# DSO_Control.net
KiCad netlist of a schematic drawn in Altium Designer
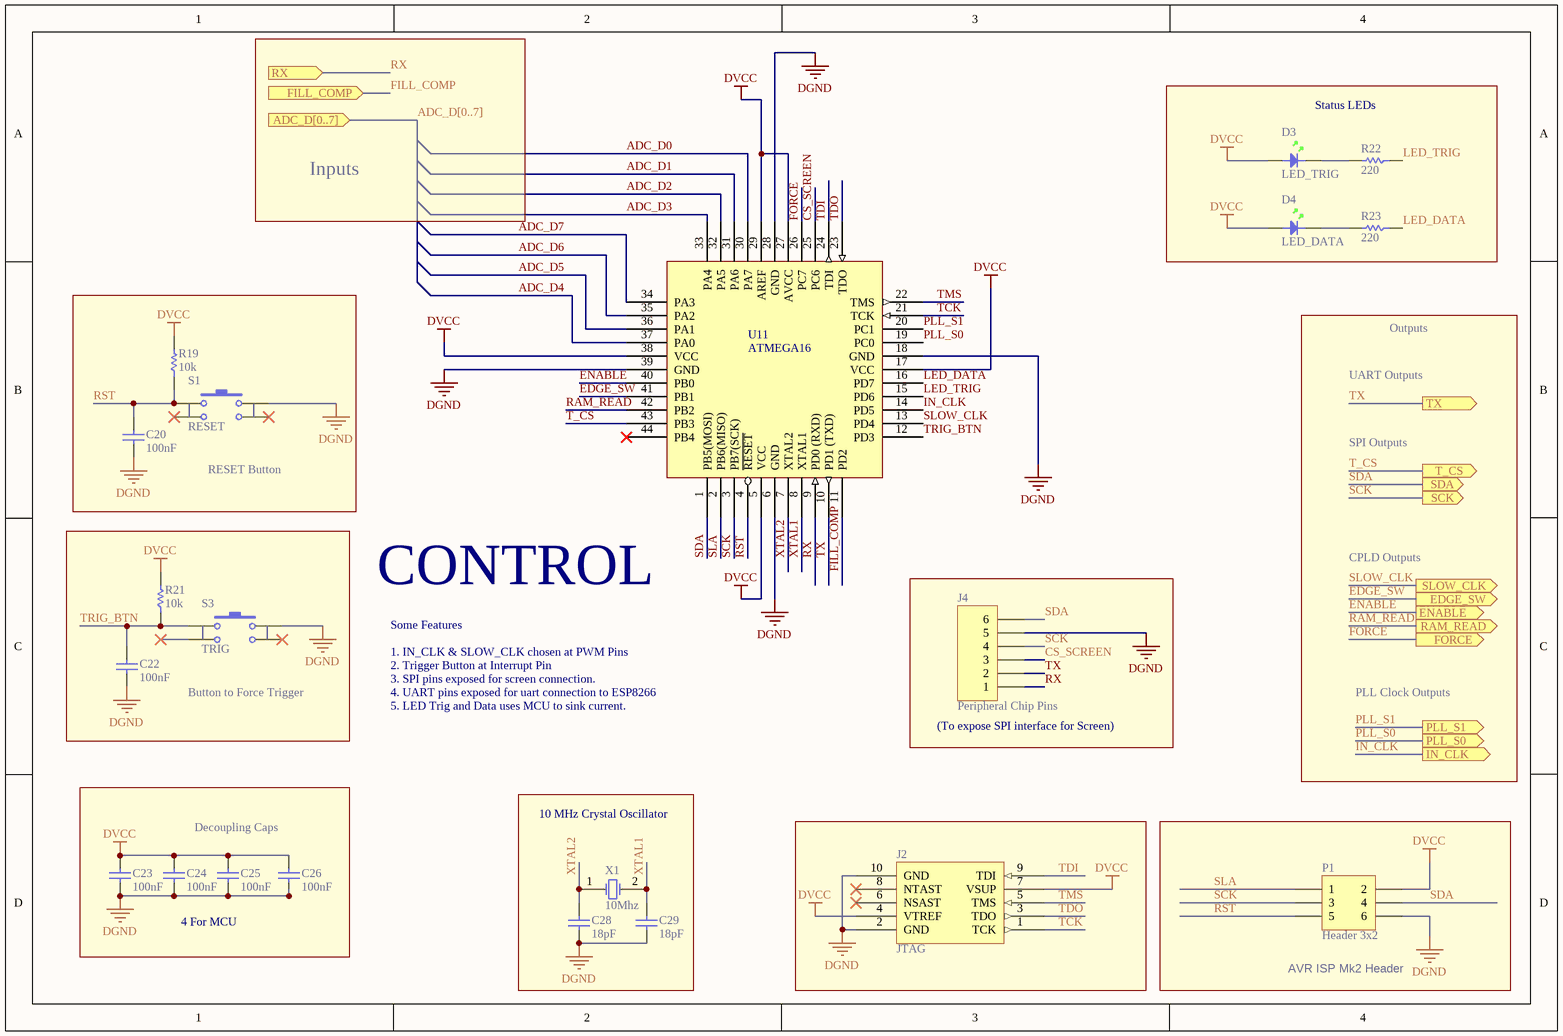
[diagram p0: DSO_Control.SchDoc]

(export (version "E")
  (design (tool "Eeschema 10.0.6"))
  (components
    (comp (ref "C20")
      (value "100nF")
      (footprint "0805C")
      (description "Capacitor")
      (fields (field (name "REVIEWED BY") "RM - 2018/08/05"))
      (libsource (lib "DSO") (part "C"))
    )
    (comp (ref "C22")
      (value "100nF")
      (footprint "0805C")
      (description "Capacitor")
      (fields (field (name "REVIEWED BY") "RM - 2018/08/05"))
      (libsource (lib "DSO") (part "C"))
    )
    (comp (ref "C23")
      (value "100nF")
      (footprint "0805C")
      (description "Capacitor")
      (fields (field (name "REVIEWED BY") "RM - 2018/08/05"))
      (libsource (lib "DSO") (part "C"))
    )
    (comp (ref "C24")
      (value "100nF")
      (footprint "0805C")
      (description "Capacitor")
      (fields (field (name "REVIEWED BY") "RM - 2018/08/05"))
      (libsource (lib "DSO") (part "C"))
    )
    (comp (ref "C25")
      (value "100nF")
      (footprint "0805C")
      (description "Capacitor")
      (fields (field (name "REVIEWED BY") "RM - 2018/08/05"))
      (libsource (lib "DSO") (part "C"))
    )
    (comp (ref "C26")
      (value "100nF")
      (footprint "0805C")
      (description "Capacitor")
      (fields (field (name "REVIEWED BY") "RM - 2018/08/05"))
      (libsource (lib "DSO") (part "C"))
    )
    (comp (ref "C28")
      (value "18pF")
      (footprint "0805C")
      (description "Capacitor")
      (fields (field (name "REVIEWED BY") "RM - 2018/08/05"))
      (libsource (lib "DSO") (part "C"))
    )
    (comp (ref "C29")
      (value "18pF")
      (footprint "0805C")
      (description "Capacitor")
      (fields (field (name "REVIEWED BY") "RM - 2018/08/05"))
      (libsource (lib "DSO") (part "C"))
    )
    (comp (ref "D3")
      (value "LED_TRIG")
      (footprint "0805D-GREEN")
      (description "Light Emitting Diode")
      (fields (field (name "REVIEWED BY") "RM - 2018/08/05"))
      (libsource (lib "DSO") (part "LED GREEN"))
    )
    (comp (ref "D4")
      (value "LED_DATA")
      (footprint "0805D-GREEN")
      (description "Light Emitting Diode")
      (fields (field (name "REVIEWED BY") "RM - 2018/08/05"))
      (libsource (lib "DSO") (part "LED GREEN"))
    )
    (comp (ref "J2")
      (value "JTAG")
      (footprint "BOXEDVERT10")
      (description "JTAG_CON")
      (fields (field (name "REVIEWED BY") "RM - 2018/08/05"))
      (libsource (lib "DSO") (part "JTAG_CON"))
    )
    (comp (ref "J4")
      (value "Peripheral Chip Pins")
      (footprint "HDR1X6")
      (description "Header, 6-Pin")
      (libsource (lib "DSO") (part "Header 6"))
    )
    (comp (ref "P1")
      (value "Header 3x2")
      (footprint "HDR3x2")
      (description "Header, 5-Pin")
      (fields (field (name "REVIEWED BY") "RM - 2018/08/05"))
      (libsource (lib "DSO") (part "Header 3x2"))
    )
    (comp (ref "R19")
      (value "10k")
      (footprint "0805")
      (description "Resistor")
      (fields (field (name "REVIEWED BY") "RM - 2018/08/05"))
      (libsource (lib "DSO") (part "R"))
    )
    (comp (ref "R21")
      (value "10k")
      (footprint "0805")
      (description "Resistor")
      (fields (field (name "REVIEWED BY") "RM - 2018/08/05"))
      (libsource (lib "DSO") (part "R"))
    )
    (comp (ref "R22")
      (value "220")
      (footprint "0805")
      (description "Resistor")
      (fields (field (name "REVIEWED BY") "RM - 2018/08/05"))
      (libsource (lib "DSO") (part "R"))
    )
    (comp (ref "R23")
      (value "220")
      (footprint "0805")
      (description "Resistor")
      (fields (field (name "REVIEWED BY") "RM - 2018/08/05"))
      (libsource (lib "DSO") (part "R"))
    )
    (comp (ref "S1")
      (value "RESET")
      (footprint "SPST PB SWITCH SMD")
      (description "Momentary Push Button Switch 1P 1T 2pins")
      (fields (field (name "REVIEWED BY") "RM - 2018/08/05"))
      (libsource (lib "DSO") (part "SW_PB_1P1T4"))
    )
    (comp (ref "S3")
      (value "TRIG")
      (footprint "SPST PB SWITCH SMD")
      (description "Momentary Push Button Switch 1P 1T 2pins")
      (fields (field (name "REVIEWED BY") "RM - 2018/08/05"))
      (libsource (lib "DSO") (part "SW_PB_1P1T4"))
    )
    (comp (ref "U11")
      (value "ATMEGA16")
      (footprint "QFP-48")
      (description "ATMEGA16 Microcontroller")
      (fields (field (name "REVIEWED BY") "RM - 2018/08/05"))
      (libsource (lib "DSO") (part "ATMEGA16"))
    )
    (comp (ref "X1")
      (value "10Mhz")
      (footprint "XTAL_FLAT_SMD")
      (description "Crystal Oscillator")
      (fields (field (name "REVIEWED BY") "RM - 2018/08/05"))
      (libsource (lib "DSO") (part "XTAL"))
    )
  )
  (nets
    (net (code "1") (name "/ADC_D0") (class "Default")
      (node (ref "U11") (pin "30") (pinfunction "PA7_30") (pintype "passive"))
    )
    (net (code "2") (name "/ADC_D1") (class "Default")
      (node (ref "U11") (pin "31") (pinfunction "PA6_31") (pintype "passive"))
    )
    (net (code "3") (name "/ADC_D2") (class "Default")
      (node (ref "U11") (pin "32") (pinfunction "PA5_32") (pintype "passive"))
    )
    (net (code "4") (name "/ADC_D3") (class "Default")
      (node (ref "U11") (pin "33") (pinfunction "PA4_33") (pintype "passive"))
    )
    (net (code "5") (name "/ADC_D4") (class "Default")
      (node (ref "U11") (pin "37") (pinfunction "PA0_37") (pintype "passive"))
    )
    (net (code "6") (name "/ADC_D5") (class "Default")
      (node (ref "U11") (pin "36") (pinfunction "PA1_36") (pintype "passive"))
    )
    (net (code "7") (name "/ADC_D6") (class "Default")
      (node (ref "U11") (pin "35") (pinfunction "PA2_35") (pintype "passive"))
    )
    (net (code "8") (name "/ADC_D7") (class "Default")
      (node (ref "U11") (pin "34") (pinfunction "PA3_34") (pintype "passive"))
    )
    (net (code "10") (name "/CS_SCREEN") (class "Default")
      (node (ref "J4") (pin "3") (pinfunction "3_3") (pintype "passive"))
      (node (ref "U11") (pin "25") (pinfunction "PC6_25") (pintype "passive"))
    )
    (net (code "11") (name "/EDGE_SW") (class "Default")
      (node (ref "U11") (pin "41") (pinfunction "PB1_41") (pintype "passive"))
    )
    (net (code "12") (name "/ENABLE") (class "Default")
      (node (ref "U11") (pin "40") (pinfunction "PB0_40") (pintype "passive"))
    )
    (net (code "13") (name "/FILL_COMP") (class "Default")
      (node (ref "U11") (pin "11") (pinfunction "PD2_11") (pintype "passive"))
    )
    (net (code "14") (name "/FORCE") (class "Default")
      (node (ref "U11") (pin "26") (pinfunction "PC7_26") (pintype "passive"))
    )
    (net (code "15") (name "/IN_CLK") (class "Default")
      (node (ref "U11") (pin "14") (pinfunction "PD5_14") (pintype "passive"))
    )
    (net (code "16") (name "/LED_DATA") (class "Default")
      (node (ref "R23") (pin "1") (pintype "passive"))
      (node (ref "U11") (pin "16") (pinfunction "PD7_16") (pintype "passive"))
    )
    (net (code "17") (name "/LED_TRIG") (class "Default")
      (node (ref "R22") (pin "1") (pintype "passive"))
      (node (ref "U11") (pin "15") (pinfunction "PD6_15") (pintype "passive"))
    )
    (net (code "18") (name "/PLL_S0") (class "Default")
      (node (ref "U11") (pin "19") (pinfunction "PC0_19") (pintype "passive"))
    )
    (net (code "19") (name "/PLL_S1") (class "Default")
      (node (ref "U11") (pin "20") (pinfunction "PC1_20") (pintype "passive"))
    )
    (net (code "20") (name "/RAM_READ") (class "Default")
      (node (ref "U11") (pin "42") (pinfunction "PB2_42") (pintype "passive"))
    )
    (net (code "21") (name "/RST") (class "Default")
      (node (ref "C20") (pin "1") (pinfunction "1_1") (pintype "passive"))
      (node (ref "P1") (pin "5") (pinfunction "5_5") (pintype "passive"))
      (node (ref "R19") (pin "1") (pintype "passive"))
      (node (ref "S1") (pin "1") (pinfunction "1_1") (pintype "passive"))
      (node (ref "U11") (pin "4") (pinfunction "~{RESET}_4") (pintype "passive"))
    )
    (net (code "22") (name "/RX") (class "Default")
      (node (ref "J4") (pin "1") (pinfunction "1_1") (pintype "passive"))
      (node (ref "U11") (pin "9") (pinfunction "PD0_(RXD)_9") (pintype "input"))
    )
    (net (code "23") (name "/SCK") (class "Default")
      (node (ref "J4") (pin "4") (pinfunction "4_4") (pintype "passive"))
      (node (ref "P1") (pin "3") (pinfunction "3_3") (pintype "passive"))
      (node (ref "U11") (pin "3") (pinfunction "PB7(SCK)_3") (pintype "passive"))
    )
    (net (code "24") (name "/SDA") (class "Default")
      (node (ref "J4") (pin "6") (pinfunction "6_6") (pintype "passive"))
      (node (ref "P1") (pin "4") (pinfunction "4_4") (pintype "passive"))
      (node (ref "U11") (pin "1") (pinfunction "PB5(MOSI)_1") (pintype "passive"))
    )
    (net (code "25") (name "/SLA") (class "Default")
      (node (ref "P1") (pin "1") (pinfunction "1_1") (pintype "passive"))
      (node (ref "U11") (pin "2") (pinfunction "PB6(MISO)_2") (pintype "passive"))
    )
    (net (code "26") (name "/SLOW_CLK") (class "Default")
      (node (ref "U11") (pin "13") (pinfunction "PD4_13") (pintype "passive"))
    )
    (net (code "27") (name "/TCK") (class "Default")
      (node (ref "J2") (pin "1") (pinfunction "TCK_1") (pintype "output"))
      (node (ref "U11") (pin "21") (pinfunction "TCK_21") (pintype "input"))
    )
    (net (code "28") (name "/TDI") (class "Default")
      (node (ref "J2") (pin "9") (pinfunction "TDI_9") (pintype "input"))
      (node (ref "U11") (pin "24") (pinfunction "TDI_24") (pintype "output"))
    )
    (net (code "29") (name "/TDO") (class "Default")
      (node (ref "J2") (pin "3") (pinfunction "TDO_3") (pintype "output"))
      (node (ref "U11") (pin "23") (pinfunction "TDO_23") (pintype "input"))
    )
    (net (code "30") (name "/TMS") (class "Default")
      (node (ref "J2") (pin "5") (pinfunction "TMS_5") (pintype "input"))
      (node (ref "U11") (pin "22") (pinfunction "TMS_22") (pintype "output"))
    )
    (net (code "31") (name "/TRIG_BTN") (class "Default")
      (node (ref "C22") (pin "1") (pinfunction "1_1") (pintype "passive"))
      (node (ref "R21") (pin "1") (pintype "passive"))
      (node (ref "S3") (pin "1") (pinfunction "1_1") (pintype "passive"))
      (node (ref "U11") (pin "12") (pinfunction "PD3_12") (pintype "passive"))
    )
    (net (code "32") (name "/TX") (class "Default")
      (node (ref "J4") (pin "2") (pinfunction "2_2") (pintype "passive"))
      (node (ref "U11") (pin "10") (pinfunction "PD1_(TXD)_10") (pintype "output"))
    )
    (net (code "33") (name "/T_CS") (class "Default")
      (node (ref "U11") (pin "43") (pinfunction "PB3_43") (pintype "passive"))
    )
    (net (code "34") (name "/XTAL1") (class "Default")
      (node (ref "C29") (pin "1") (pinfunction "1_1") (pintype "passive"))
      (node (ref "U11") (pin "8") (pinfunction "XTAL1_8") (pintype "passive"))
      (node (ref "X1") (pin "2") (pinfunction "OSC2_2") (pintype "passive"))
    )
    (net (code "35") (name "/XTAL2") (class "Default")
      (node (ref "C28") (pin "1") (pinfunction "1_1") (pintype "passive"))
      (node (ref "U11") (pin "7") (pinfunction "XTAL2_7") (pintype "passive"))
      (node (ref "X1") (pin "1") (pinfunction "OSC1_1") (pintype "passive"))
    )
    (net (code "36") (name "DGND") (class "Default")
      (node (ref "C20") (pin "2") (pinfunction "2_2") (pintype "passive"))
      (node (ref "C22") (pin "2") (pinfunction "2_2") (pintype "passive"))
      (node (ref "C23") (pin "2") (pinfunction "2_2") (pintype "passive"))
      (node (ref "C24") (pin "2") (pinfunction "2_2") (pintype "passive"))
      (node (ref "C25") (pin "2") (pinfunction "2_2") (pintype "passive"))
      (node (ref "C26") (pin "2") (pinfunction "2_2") (pintype "passive"))
      (node (ref "C28") (pin "2") (pinfunction "2_2") (pintype "passive"))
      (node (ref "C29") (pin "2") (pinfunction "2_2") (pintype "passive"))
      (node (ref "J2") (pin "10") (pinfunction "GND_10") (pintype "passive"))
      (node (ref "J2") (pin "2") (pinfunction "GND_2") (pintype "passive"))
      (node (ref "J4") (pin "5") (pinfunction "5_5") (pintype "passive"))
      (node (ref "P1") (pin "6") (pinfunction "6_6") (pintype "passive"))
      (node (ref "S1") (pin "2") (pinfunction "2_2") (pintype "passive"))
      (node (ref "S3") (pin "2") (pinfunction "2_2") (pintype "passive"))
      (node (ref "U11") (pin "18") (pinfunction "GND_18") (pintype "passive"))
      (node (ref "U11") (pin "28") (pinfunction "GND_28") (pintype "passive"))
      (node (ref "U11") (pin "39") (pinfunction "GND_39") (pintype "passive"))
      (node (ref "U11") (pin "6") (pinfunction "GND_6") (pintype "passive"))
    )
    (net (code "37") (name "DVCC") (class "Default")
      (node (ref "C23") (pin "1") (pinfunction "1_1") (pintype "passive"))
      (node (ref "C24") (pin "1") (pinfunction "1_1") (pintype "passive"))
      (node (ref "C25") (pin "1") (pinfunction "1_1") (pintype "passive"))
      (node (ref "C26") (pin "1") (pinfunction "1_1") (pintype "passive"))
      (node (ref "D3") (pin "A") (pinfunction "A_A") (pintype "passive"))
      (node (ref "D4") (pin "A") (pinfunction "A_A") (pintype "passive"))
      (node (ref "J2") (pin "4") (pinfunction "VTREF_4") (pintype "power_in"))
      (node (ref "J2") (pin "7") (pinfunction "VSUP_7") (pintype "passive"))
      (node (ref "P1") (pin "2") (pinfunction "2_2") (pintype "passive"))
      (node (ref "R19") (pin "2") (pintype "passive"))
      (node (ref "R21") (pin "2") (pintype "passive"))
      (node (ref "U11") (pin "17") (pinfunction "VCC_17") (pintype "passive"))
      (node (ref "U11") (pin "27") (pinfunction "AVCC_27") (pintype "passive"))
      (node (ref "U11") (pin "29") (pinfunction "AREF_29") (pintype "passive"))
      (node (ref "U11") (pin "38") (pinfunction "VCC_38") (pintype "passive"))
      (node (ref "U11") (pin "5") (pinfunction "VCC_5") (pintype "passive"))
    )
    (net (code "38") (name "Net-(D3-PadK)") (class "Default")
      (node (ref "D3") (pin "K") (pinfunction "K_K") (pintype "passive"))
      (node (ref "R22") (pin "2") (pintype "passive"))
    )
    (net (code "39") (name "Net-(D4-PadK)") (class "Default")
      (node (ref "D4") (pin "K") (pinfunction "K_K") (pintype "passive"))
      (node (ref "R23") (pin "2") (pintype "passive"))
    )
    (net (code "40") (name "unconnected-(J2-NSAST-Pad6)") (class "Default")
      (node (ref "J2") (pin "6") (pinfunction "NSAST_6") (pintype "passive+no_connect"))
    )
    (net (code "41") (name "unconnected-(J2-NTAST-Pad8)") (class "Default")
      (node (ref "J2") (pin "8") (pinfunction "NTAST_8") (pintype "passive+no_connect"))
    )
    (net (code "42") (name "unconnected-(S1-Pad3)") (class "Default")
      (node (ref "S1") (pin "3") (pinfunction "3_3") (pintype "passive+no_connect"))
    )
    (net (code "43") (name "unconnected-(S1-Pad4)") (class "Default")
      (node (ref "S1") (pin "4") (pinfunction "4_4") (pintype "passive+no_connect"))
    )
    (net (code "44") (name "unconnected-(S3-Pad3)") (class "Default")
      (node (ref "S3") (pin "3") (pinfunction "3_3") (pintype "passive+no_connect"))
    )
    (net (code "45") (name "unconnected-(S3-Pad4)") (class "Default")
      (node (ref "S3") (pin "4") (pinfunction "4_4") (pintype "passive+no_connect"))
    )
    (net (code "46") (name "unconnected-(U11-PB4-Pad44)") (class "Default")
      (node (ref "U11") (pin "44") (pinfunction "PB4_44") (pintype "passive+no_connect"))
    )
  )
)
